# 07_-_CPU_-_USB_ETHERNET.net
KiCad netlist of a schematic drawn in Altium Designer
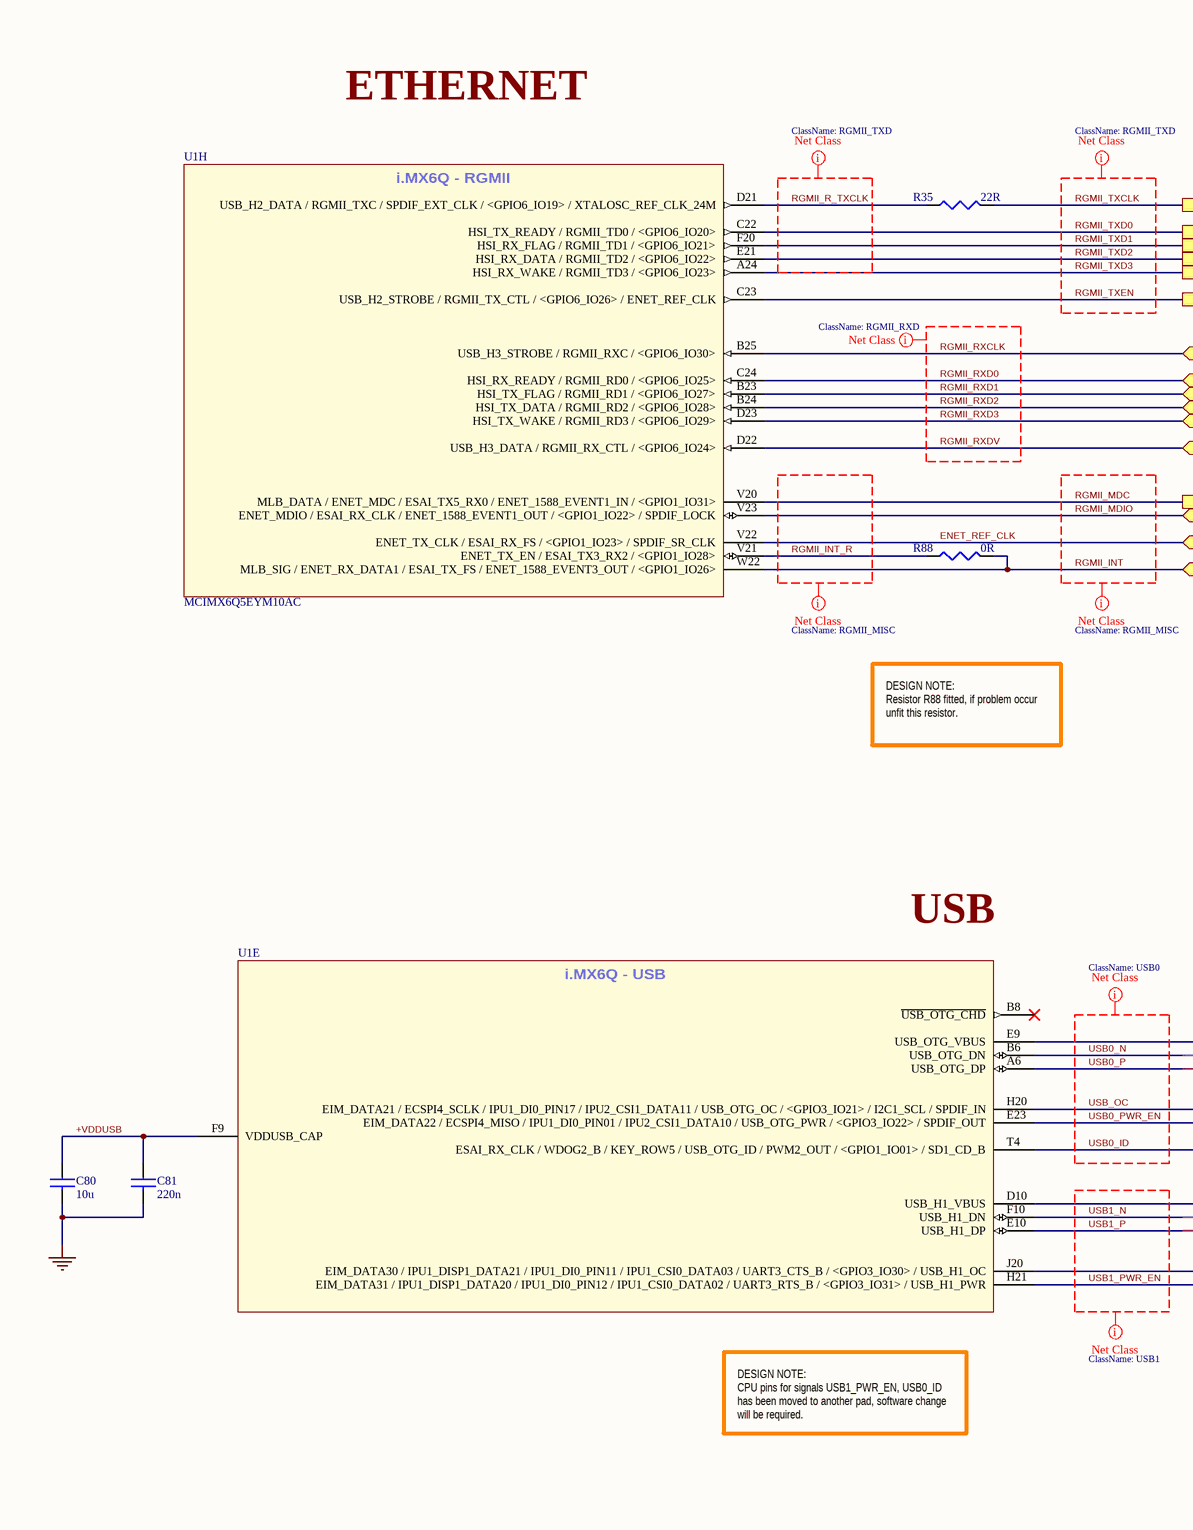
[diagram p0: [07] - CPU - USB, ETHERNET.SchDoc, left]
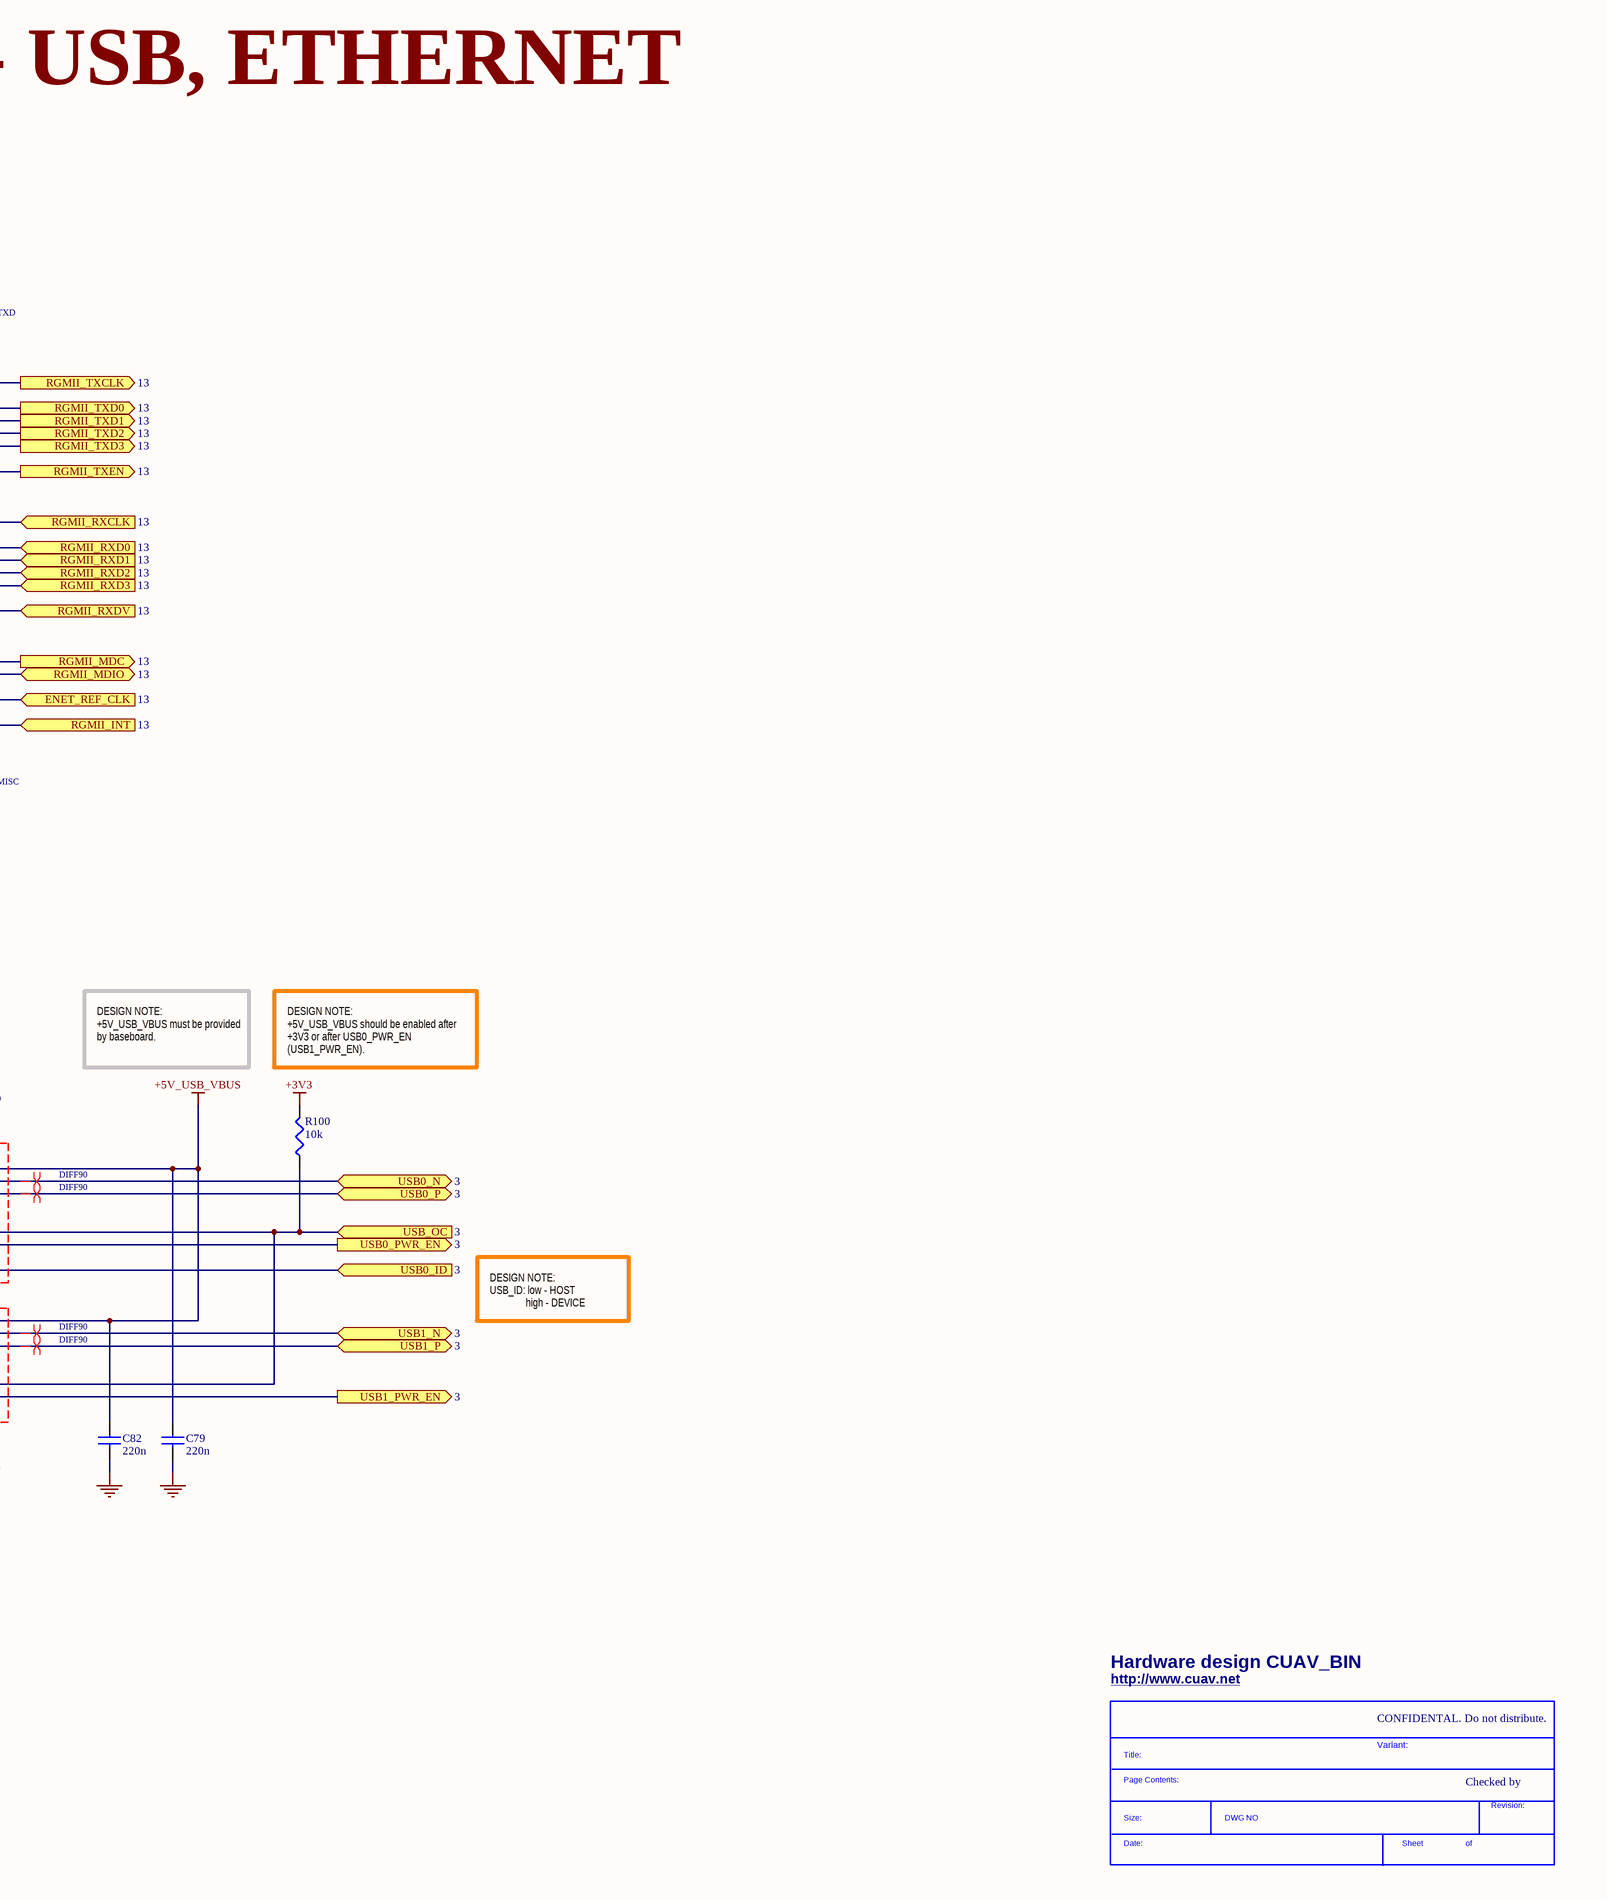
[diagram p1: [07] - CPU - USB, ETHERNET.SchDoc, right]

(export (version "E")
  (design (tool "Eeschema 10.0.6"))
  (components
    (comp (ref "*") (value "SDTitleBlock") (libsource (lib "*") (part "SDTitleBlock")))
    (comp (ref "C79")
      (value "220n")
      (footprint "C0402")
      (description "CAP CER .22UF 25V X5R 20% 0402")
      (fields
        (field (name "MANUFACTURER") "TDK Corporation")
        (field (name "MANUFACTURER PART NUMBER") "C1005X5R1E224M")
      )
      (libsource (lib "Integrated_Library_RF_FEB_2012") (part "C1005X5R1E224M"))
    )
    (comp (ref "C80")
      (value "10u")
      (footprint "C0603")
      (description "CAP CER 10UF 6.3V X5R 20% 0603")
      (fields
        (field (name "MANUFACTURER") "TDK Corporation")
        (field (name "MANUFACTURER PART NUMBER") "C1608X5R0J106M")
      )
      (libsource (lib "Integrated_Library_RF_FEB_2012") (part "C1608X5R0J106M"))
    )
    (comp (ref "C81")
      (value "220n")
      (footprint "C0402")
      (description "CAP CER .22UF 25V X5R 20% 0402")
      (fields
        (field (name "MANUFACTURER") "TDK Corporation")
        (field (name "MANUFACTURER PART NUMBER") "C1005X5R1E224M")
      )
      (libsource (lib "Integrated_Library_RF_FEB_2012") (part "C1005X5R1E224M"))
    )
    (comp (ref "C82")
      (value "220n")
      (footprint "C0402")
      (description "CAP CER .22UF 25V X5R 20% 0402")
      (fields
        (field (name "MANUFACTURER") "TDK Corporation")
        (field (name "MANUFACTURER PART NUMBER") "C1005X5R1E224M")
      )
      (libsource (lib "Integrated_Library_RF_FEB_2012") (part "C1005X5R1E224M"))
    )
    (comp (ref "R35")
      (value "22R")
      (footprint "R0402")
      (description "RES 22.0 OHM 1/16W 1% 0402 SMD")
      (fields
        (field (name "MANUFACTURER") "Yageo")
        (field (name "MANUFACTURER PART NUMBER") "RC0402FR-0722RL")
      )
      (libsource (lib "Integrated_Library_RF_FEB_2012") (part "RC0402FR-0722RL"))
    )
    (comp (ref "R88")
      (value "0R")
      (footprint "R0402")
      (description "RES 0.0 OHM 1/16W 0402 SMD")
      (fields
        (field (name "MANUFACTURER") "Yageo")
        (field (name "MANUFACTURER PART NUMBER") "RC0402JR-070RL")
      )
      (libsource (lib "Integrated_Library_RF_FEB_2012") (part "RC0402JR-070RL"))
    )
    (comp (ref "R100")
      (value "10k")
      (footprint "R0402")
      (description "RES 10.0K OHM 1/16W 1% 0402 SMD")
      (fields
        (field (name "MANUFACTURER") "Yageo")
        (field (name "MANUFACTURER PART NUMBER") "RC0402FR-0710KL")
      )
      (libsource (lib "Integrated_Library_RF_FEB_2012") (part "RC0402FR-0710KL"))
    )
    (comp (ref "U1")
      (value "MCIMX6Q5EYM10AC")
      (footprint "PBGA624")
      (description "IC MCU 32BIT ARM QUAD 624FCBGA")
      (fields
        (field (name "MANUFACTURER") "Freescale Semiconductor")
        (field (name ".CREATOR") "MM")
        (field (name ".CHECKED PCB") "MM, checked by RF")
        (field (name ".CHECKED SCH") "MM")
      )
      (libsource (lib "Schlib_RF") (part "MCIMX6Q5EYM10AC"))
    )
  )
  (nets
    (net (code "1") (name "+3V3") (class "Default")
      (node (ref "R100") (pin "2") (pinfunction "2_2") (pintype "passive"))
    )
    (net (code "2") (name "+5V_USB_VBUS") (class "Default")
      (node (ref "C79") (pin "1") (pinfunction "1_1") (pintype "passive"))
      (node (ref "C82") (pin "1") (pinfunction "1_1") (pintype "passive"))
      (node (ref "U1") (pin "D10") (pinfunction "USB_H1_VBUS_D10") (pintype "power_in"))
      (node (ref "U1") (pin "E9") (pinfunction "USB_OTG_VBUS_E9") (pintype "power_in"))
    )
    (net (code "3") (name "/+VDDUSB") (class "Default")
      (node (ref "C80") (pin "1") (pinfunction "1_1") (pintype "passive"))
      (node (ref "C81") (pin "1") (pinfunction "1_1") (pintype "passive"))
      (node (ref "U1") (pin "F9") (pinfunction "VDDUSB_CAP_F9") (pintype "power_in"))
    )
    (net (code "4") (name "/ENET_REF_CLK") (class "Default")
      (node (ref "U1") (pin "V22") (pinfunction "ENET_TX_CLK_/_ESAI_RX_FS_/_<GPIO1_IO23>_/_SPDIF_SR_CLK_V22") (pintype "passive"))
    )
    (net (code "5") (name "/RGMII_INT") (class "Default")
      (node (ref "R88") (pin "2") (pinfunction "2_2") (pintype "passive"))
      (node (ref "U1") (pin "W22") (pinfunction "MLB_SIG_/_ENET_RX_DATA1_/_ESAI_TX_FS_/_ENET_1588_EVENT3_OUT_/_<GPIO1_IO26>_W22") (pintype "passive"))
    )
    (net (code "6") (name "/RGMII_INT_R") (class "Default")
      (node (ref "R88") (pin "1") (pinfunction "1_1") (pintype "passive"))
      (node (ref "U1") (pin "V21") (pinfunction "ENET_TX_EN_/_ESAI_TX3_RX2_/_<GPIO1_IO28>_V21") (pintype "bidirectional"))
    )
    (net (code "7") (name "/RGMII_MDC") (class "Default")
      (node (ref "U1") (pin "V20") (pinfunction "MLB_DATA_/_ENET_MDC_/_ESAI_TX5_RX0_/_ENET_1588_EVENT1_IN_/_<GPIO1_IO31>_V20") (pintype "passive"))
    )
    (net (code "8") (name "/RGMII_MDIO") (class "Default")
      (node (ref "U1") (pin "V23") (pinfunction "ENET_MDIO_/_ESAI_RX_CLK_/_ENET_1588_EVENT1_OUT_/_<GPIO1_IO22>_/_SPDIF_LOCK_V23") (pintype "bidirectional"))
    )
    (net (code "9") (name "/RGMII_RXCLK") (class "Default")
      (node (ref "U1") (pin "B25") (pinfunction "USB_H3_STROBE_/_RGMII_RXC_/_<GPIO6_IO30>_B25") (pintype "input"))
    )
    (net (code "10") (name "/RGMII_RXD0") (class "Default")
      (node (ref "U1") (pin "C24") (pinfunction "HSI_RX_READY_/_RGMII_RD0_/_<GPIO6_IO25>_C24") (pintype "input"))
    )
    (net (code "11") (name "/RGMII_RXD1") (class "Default")
      (node (ref "U1") (pin "B23") (pinfunction "HSI_TX_FLAG_/_RGMII_RD1_/_<GPIO6_IO27>_B23") (pintype "input"))
    )
    (net (code "12") (name "/RGMII_RXD2") (class "Default")
      (node (ref "U1") (pin "B24") (pinfunction "HSI_TX_DATA_/_RGMII_RD2_/_<GPIO6_IO28>_B24") (pintype "input"))
    )
    (net (code "13") (name "/RGMII_RXD3") (class "Default")
      (node (ref "U1") (pin "D23") (pinfunction "HSI_TX_WAKE_/_RGMII_RD3_/_<GPIO6_IO29>_D23") (pintype "input"))
    )
    (net (code "14") (name "/RGMII_RXDV") (class "Default")
      (node (ref "U1") (pin "D22") (pinfunction "USB_H3_DATA_/_RGMII_RX_CTL_/_<GPIO6_IO24>_D22") (pintype "input"))
    )
    (net (code "15") (name "/RGMII_R_TXCLK") (class "Default")
      (node (ref "R35") (pin "1") (pinfunction "1_1") (pintype "passive"))
      (node (ref "U1") (pin "D21") (pinfunction "USB_H2_DATA_/_RGMII_TXC_/_SPDIF_EXT_CLK_/_<GPIO6_IO19>_/_XTALOSC_REF_CLK_24M_D21") (pintype "output"))
    )
    (net (code "16") (name "/RGMII_TXCLK") (class "Default")
      (node (ref "R35") (pin "2") (pinfunction "2_2") (pintype "passive"))
    )
    (net (code "17") (name "/RGMII_TXD0") (class "Default")
      (node (ref "U1") (pin "C22") (pinfunction "HSI_TX_READY_/_RGMII_TD0_/_<GPIO6_IO20>_C22") (pintype "output"))
    )
    (net (code "18") (name "/RGMII_TXD1") (class "Default")
      (node (ref "U1") (pin "F20") (pinfunction "HSI_RX_FLAG_/_RGMII_TD1_/_<GPIO6_IO21>_F20") (pintype "output"))
    )
    (net (code "19") (name "/RGMII_TXD2") (class "Default")
      (node (ref "U1") (pin "E21") (pinfunction "HSI_RX_DATA_/_RGMII_TD2_/_<GPIO6_IO22>_E21") (pintype "output"))
    )
    (net (code "20") (name "/RGMII_TXD3") (class "Default")
      (node (ref "U1") (pin "A24") (pinfunction "HSI_RX_WAKE_/_RGMII_TD3_/_<GPIO6_IO23>_A24") (pintype "output"))
    )
    (net (code "21") (name "/RGMII_TXEN") (class "Default")
      (node (ref "U1") (pin "C23") (pinfunction "USB_H2_STROBE_/_RGMII_TX_CTL_/_<GPIO6_IO26>_/_ENET_REF_CLK_C23") (pintype "output"))
    )
    (net (code "22") (name "/USB0_ID") (class "Default")
      (node (ref "U1") (pin "T4") (pinfunction "ESAI_RX_CLK_/_WDOG2_B_/_KEY_ROW5_/_USB_OTG_ID_/_PWM2_OUT_/_<GPIO1_IO01>_/_SD1_CD_B_T4") (pintype "passive"))
    )
    (net (code "23") (name "/USB0_N") (class "Default")
      (node (ref "U1") (pin "B6") (pinfunction "USB_OTG_DN_B6") (pintype "bidirectional"))
    )
    (net (code "24") (name "/USB0_P") (class "Default")
      (node (ref "U1") (pin "A6") (pinfunction "USB_OTG_DP_A6") (pintype "bidirectional"))
    )
    (net (code "25") (name "/USB0_PWR_EN") (class "Default")
      (node (ref "U1") (pin "E23") (pinfunction "EIM_DATA22_/_ECSPI4_MISO_/_IPU1_DI0_PIN01_/_IPU2_CSI1_DATA10_/_USB_OTG_PWR_/_<GPIO3_IO22>_/_SPDIF_OUT_E23") (pintype "passive"))
    )
    (net (code "26") (name "/USB1_N") (class "Default")
      (node (ref "U1") (pin "F10") (pinfunction "USB_H1_DN_F10") (pintype "bidirectional"))
    )
    (net (code "27") (name "/USB1_P") (class "Default")
      (node (ref "U1") (pin "E10") (pinfunction "USB_H1_DP_E10") (pintype "bidirectional"))
    )
    (net (code "28") (name "/USB1_PWR_EN") (class "Default")
      (node (ref "U1") (pin "H21") (pinfunction "EIM_DATA31_/_IPU1_DISP1_DATA20_/_IPU1_DI0_PIN12_/_IPU1_CSI0_DATA02_/_UART3_RTS_B_/_<GPIO3_IO31>_/_USB_H1_PWR_H21") (pintype "passive"))
    )
    (net (code "29") (name "/USB_OC") (class "Default")
      (node (ref "R100") (pin "1") (pinfunction "1_1") (pintype "passive"))
      (node (ref "U1") (pin "H20") (pinfunction "EIM_DATA21_/_ECSPI4_SCLK_/_IPU1_DI0_PIN17_/_IPU2_CSI1_DATA11_/_USB_OTG_OC_/_<GPIO3_IO21>_/_I2C1_SCL_/_SPDIF_IN_H20") (pintype "passive"))
      (node (ref "U1") (pin "J20") (pinfunction "EIM_DATA30_/_IPU1_DISP1_DATA21_/_IPU1_DI0_PIN11_/_IPU1_CSI0_DATA03_/_UART3_CTS_B_/_<GPIO3_IO30>_/_USB_H1_OC_J20") (pintype "passive"))
    )
    (net (code "30") (name "GND") (class "Default")
      (node (ref "C79") (pin "2") (pinfunction "2_2") (pintype "passive"))
      (node (ref "C80") (pin "2") (pinfunction "2_2") (pintype "passive"))
      (node (ref "C81") (pin "2") (pinfunction "2_2") (pintype "passive"))
      (node (ref "C82") (pin "2") (pinfunction "2_2") (pintype "passive"))
    )
    (net (code "31") (name "unconnected-(U1E-~{USB_OTG_CHD}-PadB8)") (class "Default")
      (node (ref "U1") (pin "B8") (pinfunction "~{USB_OTG_CHD}_B8") (pintype "output+no_connect"))
    )
  )
)
